# Renesas_Raspi1_Add_On_V2.net
KiCad netlist of a schematic drawn in EAGLE
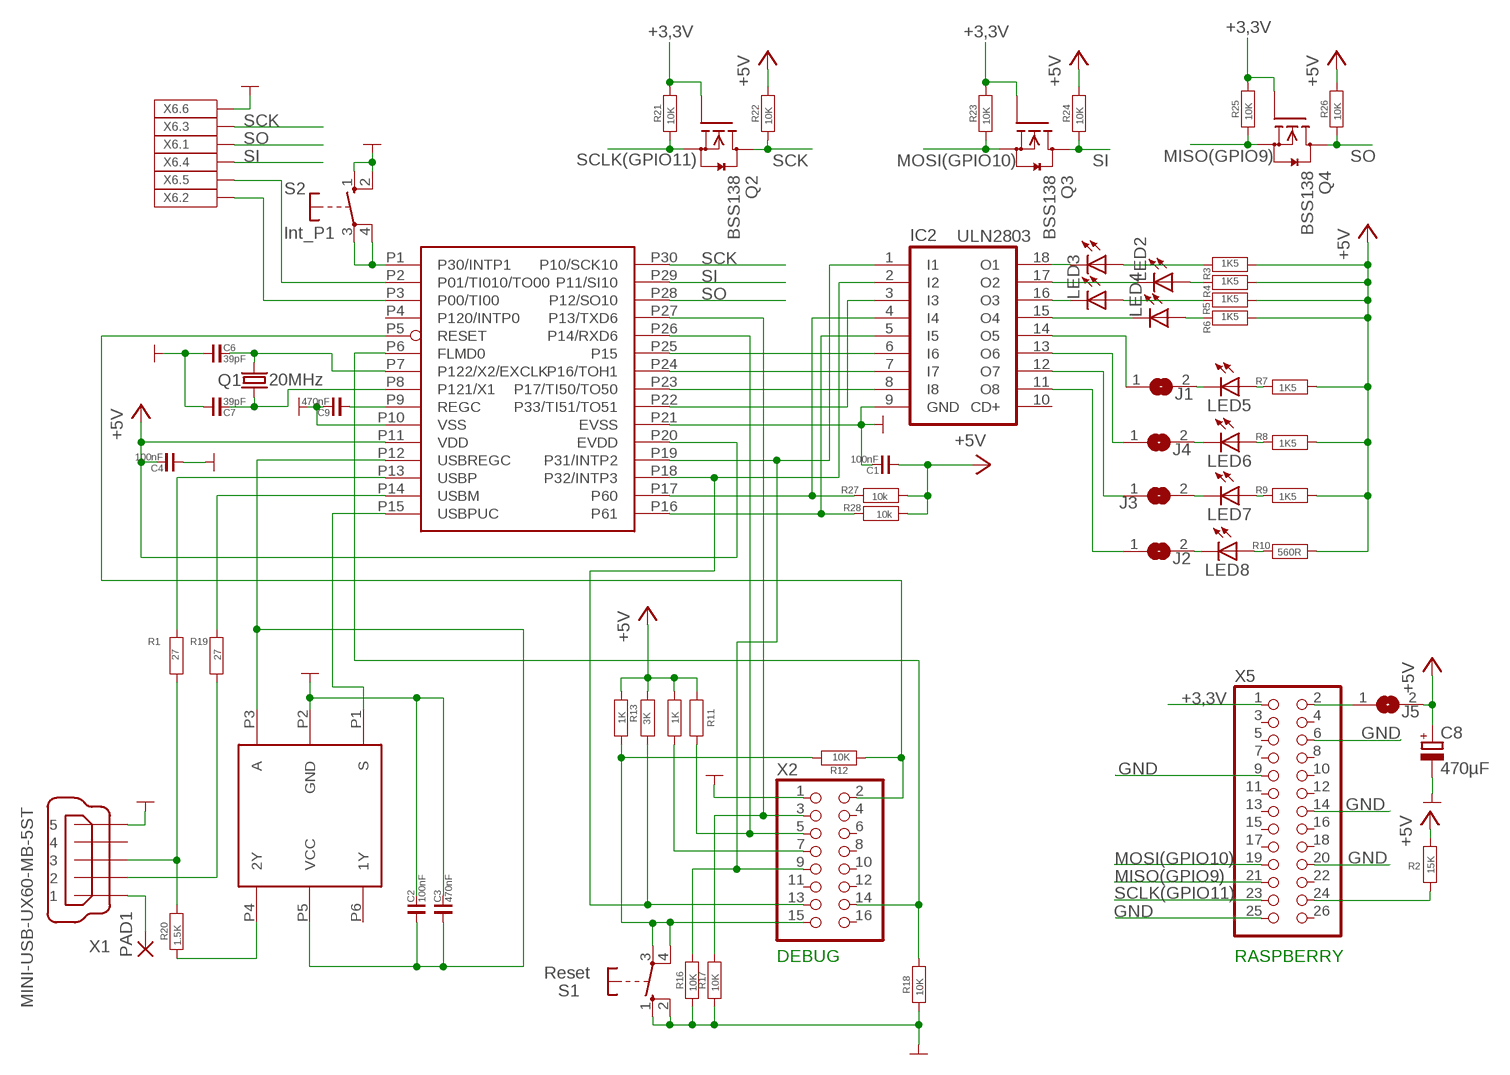
[diagram p0: schematic, sheet 1]

(export (version "E")
  (design (tool "Eeschema 10.0.6"))
  (components
    (comp (ref "C1")
      (value "100nF")
      (footprint "eagle-import:0603")
      (libsource (lib "eagle-import") (part "C-0603"))
    )
    (comp (ref "C2")
      (value "100nF")
      (footprint "eagle-import:0603")
      (libsource (lib "eagle-import") (part "C-0603"))
    )
    (comp (ref "C3")
      (value "470nF")
      (footprint "eagle-import:0603")
      (libsource (lib "eagle-import") (part "C-0603"))
    )
    (comp (ref "C4")
      (value "100nF")
      (footprint "eagle-import:0603")
      (libsource (lib "eagle-import") (part "C-0603"))
    )
    (comp (ref "C6")
      (value "39pF")
      (footprint "eagle-import:0603")
      (libsource (lib "eagle-import") (part "C-0603"))
    )
    (comp (ref "C7")
      (value "39pF")
      (footprint "eagle-import:0603")
      (libsource (lib "eagle-import") (part "C-0603"))
    )
    (comp (ref "C8")
      (value "470µF")
      (footprint "eagle-import:SANYO-OSCON_SMD_F8")
      (libsource (lib "eagle-import") (part "CPOL-EUSANYO_SMD_F8"))
    )
    (comp (ref "C9")
      (value "470nF")
      (footprint "eagle-import:0603")
      (libsource (lib "eagle-import") (part "C-0603"))
    )
    (comp (ref "IC1")
      (value "78F0730_CAB_AX")
      (footprint "eagle-import:SSOP30")
      (libsource (lib "eagle-import") (part "78F0730_CAB_AX"))
    )
    (comp (ref "IC2")
      (value "ULN2803")
      (footprint "eagle-import:SOJ18-4")
      (libsource (lib "eagle-import") (part "ULN2803"))
    )
    (comp (ref "IC3")
      (value "74LVC1G18")
      (footprint "eagle-import:74LVC1G18")
      (libsource (lib "eagle-import") (part "74LVC1G18"))
    )
    (comp (ref "J1") (value "SJ") (footprint "eagle-import:SJ") (libsource (lib "eagle-import") (part "SJ")))
    (comp (ref "J2") (value "SJ") (footprint "eagle-import:SJ") (libsource (lib "eagle-import") (part "SJ")))
    (comp (ref "J3") (value "SJ") (footprint "eagle-import:SJ") (libsource (lib "eagle-import") (part "SJ")))
    (comp (ref "J4") (value "SJ") (footprint "eagle-import:SJ") (libsource (lib "eagle-import") (part "SJ")))
    (comp (ref "J5") (value "SJ") (footprint "eagle-import:SJ") (libsource (lib "eagle-import") (part "SJ")))
    (comp (ref "LED1")
      (value "LEDCHIP-LED0603")
      (footprint "eagle-import:CHIP-LED0603")
      (libsource (lib "eagle-import") (part "LEDCHIP-LED0603"))
    )
    (comp (ref "LED2")
      (value "LEDCHIP-LED0603")
      (footprint "eagle-import:CHIP-LED0603")
      (libsource (lib "eagle-import") (part "LEDCHIP-LED0603"))
    )
    (comp (ref "LED3")
      (value "LEDCHIP-LED0603")
      (footprint "eagle-import:CHIP-LED0603")
      (libsource (lib "eagle-import") (part "LEDCHIP-LED0603"))
    )
    (comp (ref "LED4")
      (value "LEDCHIP-LED0603")
      (footprint "eagle-import:CHIP-LED0603")
      (libsource (lib "eagle-import") (part "LEDCHIP-LED0603"))
    )
    (comp (ref "LED5")
      (value "LEDCHIP-LED0603")
      (footprint "eagle-import:CHIP-LED0603")
      (libsource (lib "eagle-import") (part "LEDCHIP-LED0603"))
    )
    (comp (ref "LED6")
      (value "LEDCHIP-LED0603")
      (footprint "eagle-import:CHIP-LED0603")
      (libsource (lib "eagle-import") (part "LEDCHIP-LED0603"))
    )
    (comp (ref "LED7")
      (value "LEDCHIP-LED0603")
      (footprint "eagle-import:CHIP-LED0603")
      (libsource (lib "eagle-import") (part "LEDCHIP-LED0603"))
    )
    (comp (ref "LED8")
      (value "LEDCHIP-LED0603")
      (footprint "eagle-import:CHIP-LED0603")
      (libsource (lib "eagle-import") (part "LEDCHIP-LED0603"))
    )
    (comp (ref "PAD1")
      (value "1,6/0,8")
      (footprint "eagle-import:1,6_0,8")
      (libsource (lib "eagle-import") (part "1,6/0,8"))
    )
    (comp (ref "Q1")
      (value "20MHz")
      (footprint "eagle-import:HC49UP")
      (libsource (lib "eagle-import") (part "CRYSTALHC49UP"))
    )
    (comp (ref "Q2")
      (value "BSS138")
      (footprint "eagle-import:SOT23")
      (libsource (lib "eagle-import") (part "BSS138"))
    )
    (comp (ref "Q3")
      (value "BSS138")
      (footprint "eagle-import:SOT23")
      (libsource (lib "eagle-import") (part "BSS138"))
    )
    (comp (ref "Q4")
      (value "BSS138")
      (footprint "eagle-import:SOT23")
      (libsource (lib "eagle-import") (part "BSS138"))
    )
    (comp (ref "R1")
      (value "27")
      (footprint "eagle-import:0603")
      (libsource (lib "eagle-import") (part "R-0603"))
    )
    (comp (ref "R2")
      (value "15K")
      (footprint "eagle-import:0603")
      (libsource (lib "eagle-import") (part "R-0603"))
    )
    (comp (ref "R3")
      (value "1K5")
      (footprint "eagle-import:0603")
      (libsource (lib "eagle-import") (part "R-0603"))
    )
    (comp (ref "R4")
      (value "1K5")
      (footprint "eagle-import:0603")
      (libsource (lib "eagle-import") (part "R-0603"))
    )
    (comp (ref "R5")
      (value "1K5")
      (footprint "eagle-import:0603")
      (libsource (lib "eagle-import") (part "R-0603"))
    )
    (comp (ref "R6")
      (value "1K5")
      (footprint "eagle-import:0603")
      (libsource (lib "eagle-import") (part "R-0603"))
    )
    (comp (ref "R7")
      (value "1K5")
      (footprint "eagle-import:0603")
      (libsource (lib "eagle-import") (part "R-0603"))
    )
    (comp (ref "R8")
      (value "1K5")
      (footprint "eagle-import:0603")
      (libsource (lib "eagle-import") (part "R-0603"))
    )
    (comp (ref "R9")
      (value "1K5")
      (footprint "eagle-import:0603")
      (libsource (lib "eagle-import") (part "R-0603"))
    )
    (comp (ref "R10")
      (value "560R")
      (footprint "eagle-import:0603")
      (libsource (lib "eagle-import") (part "R-0603"))
    )
    (comp (ref "R11")
      (value "3K")
      (footprint "eagle-import:0603")
      (libsource (lib "eagle-import") (part "R-0603"))
    )
    (comp (ref "R12")
      (value "10K")
      (footprint "eagle-import:0603")
      (libsource (lib "eagle-import") (part "R-0603"))
    )
    (comp (ref "R13")
      (value "3K")
      (footprint "eagle-import:0603")
      (libsource (lib "eagle-import") (part "R-0603"))
    )
    (comp (ref "R14")
      (value "1K")
      (footprint "eagle-import:0603")
      (libsource (lib "eagle-import") (part "R-0603"))
    )
    (comp (ref "R15")
      (value "1K")
      (footprint "eagle-import:0603")
      (libsource (lib "eagle-import") (part "R-0603"))
    )
    (comp (ref "R16")
      (value "10K")
      (footprint "eagle-import:0603")
      (libsource (lib "eagle-import") (part "R-0603"))
    )
    (comp (ref "R17")
      (value "10K")
      (footprint "eagle-import:0603")
      (libsource (lib "eagle-import") (part "R-0603"))
    )
    (comp (ref "R18")
      (value "10K")
      (footprint "eagle-import:0603")
      (libsource (lib "eagle-import") (part "R-0603"))
    )
    (comp (ref "R19")
      (value "27")
      (footprint "eagle-import:0603")
      (libsource (lib "eagle-import") (part "R-0603"))
    )
    (comp (ref "R20")
      (value "1.5K")
      (footprint "eagle-import:0603")
      (libsource (lib "eagle-import") (part "R-0603"))
    )
    (comp (ref "R21")
      (value "10K")
      (footprint "eagle-import:0603")
      (libsource (lib "eagle-import") (part "R-0603"))
    )
    (comp (ref "R22")
      (value "10K")
      (footprint "eagle-import:0603")
      (libsource (lib "eagle-import") (part "R-0603"))
    )
    (comp (ref "R23")
      (value "10K")
      (footprint "eagle-import:0603")
      (libsource (lib "eagle-import") (part "R-0603"))
    )
    (comp (ref "R24")
      (value "10K")
      (footprint "eagle-import:0603")
      (libsource (lib "eagle-import") (part "R-0603"))
    )
    (comp (ref "R25")
      (value "10K")
      (footprint "eagle-import:0603")
      (libsource (lib "eagle-import") (part "R-0603"))
    )
    (comp (ref "R26")
      (value "10K")
      (footprint "eagle-import:0603")
      (libsource (lib "eagle-import") (part "R-0603"))
    )
    (comp (ref "R27")
      (value "10k")
      (footprint "eagle-import:0603")
      (libsource (lib "eagle-import") (part "R-0603"))
    )
    (comp (ref "R28")
      (value "10k")
      (footprint "eagle-import:0603")
      (libsource (lib "eagle-import") (part "R-0603"))
    )
    (comp (ref "S1")
      (value "Reset")
      (footprint "eagle-import:DT6")
      (libsource (lib "eagle-import") (part "DT6"))
    )
    (comp (ref "S2")
      (value "Int_P1")
      (footprint "eagle-import:DT6")
      (libsource (lib "eagle-import") (part "DT6"))
    )
    (comp (ref "X1")
      (value "MINI-USB-UX60-MB-5ST")
      (footprint "eagle-import:UX60-MB-5ST")
      (libsource (lib "eagle-import") (part "MINI-USB-UX60-MB-5ST"))
    )
    (comp (ref "X2")
      (value "PINHD-2X8")
      (footprint "eagle-import:2X08")
      (libsource (lib "eagle-import") (part "PINHD-2X8"))
    )
    (comp (ref "X5")
      (value "PINHD-2X13")
      (footprint "eagle-import:2X13")
      (libsource (lib "eagle-import") (part "PINHD-2X13"))
    )
    (comp (ref "X6")
      (value "2X3")
      (footprint "eagle-import:2X3")
      (libsource (lib "eagle-import") (part "2X3"))
    )
  )
  (nets
    (net (code "1") (name "+5V") (class "Default")
      (node (ref "C1") (pin "1") (pinfunction "1_1") (pintype "passive"))
      (node (ref "C4") (pin "2") (pinfunction "2_2") (pintype "passive"))
      (node (ref "C8") (pin "+") (pinfunction "+_+") (pintype "passive"))
      (node (ref "IC1") (pin "P11") (pinfunction "VDD_P11") (pintype "bidirectional"))
      (node (ref "IC1") (pin "P20") (pinfunction "EVDD_P20") (pintype "bidirectional"))
      (node (ref "J5") (pin "2") (pinfunction "2_2") (pintype "passive"))
      (node (ref "R10") (pin "1") (pinfunction "1_1") (pintype "passive"))
      (node (ref "R11") (pin "1") (pinfunction "1_1") (pintype "passive"))
      (node (ref "R13") (pin "2") (pinfunction "2_2") (pintype "passive"))
      (node (ref "R14") (pin "1") (pinfunction "1_1") (pintype "passive"))
      (node (ref "R15") (pin "1") (pinfunction "1_1") (pintype "passive"))
      (node (ref "R2") (pin "1") (pinfunction "1_1") (pintype "passive"))
      (node (ref "R22") (pin "1") (pinfunction "1_1") (pintype "passive"))
      (node (ref "R24") (pin "1") (pinfunction "1_1") (pintype "passive"))
      (node (ref "R26") (pin "1") (pinfunction "1_1") (pintype "passive"))
      (node (ref "R27") (pin "1") (pinfunction "1_1") (pintype "passive"))
      (node (ref "R28") (pin "1") (pinfunction "1_1") (pintype "passive"))
      (node (ref "R3") (pin "2") (pinfunction "2_2") (pintype "passive"))
      (node (ref "R4") (pin "2") (pinfunction "2_2") (pintype "passive"))
      (node (ref "R5") (pin "2") (pinfunction "2_2") (pintype "passive"))
      (node (ref "R6") (pin "2") (pinfunction "2_2") (pintype "passive"))
      (node (ref "R7") (pin "1") (pinfunction "1_1") (pintype "passive"))
      (node (ref "R8") (pin "1") (pinfunction "1_1") (pintype "passive"))
      (node (ref "R9") (pin "1") (pinfunction "1_1") (pintype "passive"))
    )
    (net (code "2") (name "/+3,3V") (class "Default")
      (node (ref "Q2") (pin "1") (pinfunction "G_1") (pintype "passive"))
      (node (ref "Q3") (pin "1") (pinfunction "G_1") (pintype "passive"))
      (node (ref "Q4") (pin "1") (pinfunction "G_1") (pintype "passive"))
      (node (ref "R21") (pin "1") (pinfunction "1_1") (pintype "passive"))
      (node (ref "R23") (pin "1") (pinfunction "1_1") (pintype "passive"))
      (node (ref "R25") (pin "1") (pinfunction "1_1") (pintype "passive"))
      (node (ref "X5") (pin "1") (pinfunction "1_1") (pintype "passive"))
    )
    (net (code "3") (name "/MISO(GPIO9)") (class "Default")
      (node (ref "Q4") (pin "2") (pinfunction "S_2") (pintype "passive"))
      (node (ref "R25") (pin "2") (pinfunction "2_2") (pintype "passive"))
      (node (ref "X5") (pin "21") (pinfunction "21_21") (pintype "passive"))
    )
    (net (code "4") (name "/MOSI(GPIO10)") (class "Default")
      (node (ref "Q3") (pin "2") (pinfunction "S_2") (pintype "passive"))
      (node (ref "R23") (pin "2") (pinfunction "2_2") (pintype "passive"))
      (node (ref "X5") (pin "19") (pinfunction "19_19") (pintype "passive"))
    )
    (net (code "5") (name "/N$14") (class "Default")
      (node (ref "R12") (pin "1") (pinfunction "1_1") (pintype "passive"))
      (node (ref "R15") (pin "2") (pinfunction "2_2") (pintype "passive"))
      (node (ref "S1") (pin "3") (pinfunction "P_3") (pintype "passive"))
      (node (ref "S1") (pin "4") (pinfunction "P_4") (pintype "passive"))
      (node (ref "X2") (pin "15") (pinfunction "15_15") (pintype "passive"))
    )
    (net (code "6") (name "/SCK") (class "Default")
      (node (ref "IC1") (pin "P30") (pinfunction "P10/SCK10_P30") (pintype "bidirectional"))
      (node (ref "Q2") (pin "3") (pinfunction "D_3") (pintype "passive"))
      (node (ref "R22") (pin "2") (pinfunction "2_2") (pintype "passive"))
      (node (ref "X6") (pin "3") (pinfunction "I_3") (pintype "passive"))
    )
    (net (code "7") (name "/SCLK(GPIO11)") (class "Default")
      (node (ref "Q2") (pin "2") (pinfunction "S_2") (pintype "passive"))
      (node (ref "R21") (pin "2") (pinfunction "2_2") (pintype "passive"))
      (node (ref "X5") (pin "23") (pinfunction "23_23") (pintype "passive"))
    )
    (net (code "8") (name "/SI") (class "Default")
      (node (ref "IC1") (pin "P29") (pinfunction "P11/SI10_P29") (pintype "bidirectional"))
      (node (ref "Q3") (pin "3") (pinfunction "D_3") (pintype "passive"))
      (node (ref "R24") (pin "2") (pinfunction "2_2") (pintype "passive"))
      (node (ref "X6") (pin "4") (pinfunction "I_4") (pintype "passive"))
    )
    (net (code "9") (name "/SO") (class "Default")
      (node (ref "IC1") (pin "P28") (pinfunction "P12/SO10_P28") (pintype "bidirectional"))
      (node (ref "Q4") (pin "3") (pinfunction "D_3") (pintype "passive"))
      (node (ref "R26") (pin "2") (pinfunction "2_2") (pintype "passive"))
      (node (ref "X6") (pin "1") (pinfunction "I_1") (pintype "passive"))
    )
    (net (code "10") (name "GND") (class "Default")
      (node (ref "C1") (pin "2") (pinfunction "2_2") (pintype "passive"))
      (node (ref "C2") (pin "2") (pinfunction "2_2") (pintype "passive"))
      (node (ref "C3") (pin "2") (pinfunction "2_2") (pintype "passive"))
      (node (ref "C4") (pin "1") (pinfunction "1_1") (pintype "passive"))
      (node (ref "C6") (pin "1") (pinfunction "1_1") (pintype "passive"))
      (node (ref "C7") (pin "1") (pinfunction "1_1") (pintype "passive"))
      (node (ref "C8") (pin "-") (pinfunction "-_-") (pintype "passive"))
      (node (ref "C9") (pin "2") (pinfunction "2_2") (pintype "passive"))
      (node (ref "IC1") (pin "P10") (pinfunction "VSS_P10") (pintype "bidirectional"))
      (node (ref "IC1") (pin "P21") (pinfunction "EVSS_P21") (pintype "bidirectional"))
      (node (ref "IC2") (pin "9") (pinfunction "GND_9") (pintype "power_in"))
      (node (ref "IC3") (pin "P2") (pinfunction "GND_P2") (pintype "bidirectional"))
      (node (ref "R16") (pin "2") (pinfunction "2_2") (pintype "passive"))
      (node (ref "R17") (pin "2") (pinfunction "2_2") (pintype "passive"))
      (node (ref "R18") (pin "2") (pinfunction "2_2") (pintype "passive"))
      (node (ref "S1") (pin "1") (pinfunction "S_1") (pintype "passive"))
      (node (ref "S1") (pin "2") (pinfunction "S_2") (pintype "passive"))
      (node (ref "S2") (pin "1") (pinfunction "S_1") (pintype "passive"))
      (node (ref "S2") (pin "2") (pinfunction "S_2") (pintype "passive"))
      (node (ref "X1") (pin "5") (pinfunction "5_5") (pintype "input"))
      (node (ref "X2") (pin "1") (pinfunction "1_1") (pintype "passive"))
      (node (ref "X5") (pin "14") (pinfunction "14_14") (pintype "passive"))
      (node (ref "X5") (pin "20") (pinfunction "20_20") (pintype "passive"))
      (node (ref "X5") (pin "25") (pinfunction "25_25") (pintype "passive"))
      (node (ref "X5") (pin "6") (pinfunction "6_6") (pintype "passive"))
      (node (ref "X5") (pin "9") (pinfunction "9_9") (pintype "passive"))
      (node (ref "X6") (pin "6") (pinfunction "I_6") (pintype "passive"))
    )
    (net (code "11") (name "Net-(IC1-FLMD0)") (class "Default")
      (node (ref "IC1") (pin "P6") (pinfunction "FLMD0_P6") (pintype "bidirectional"))
      (node (ref "R18") (pin "1") (pinfunction "1_1") (pintype "passive"))
      (node (ref "X2") (pin "14") (pinfunction "14_14") (pintype "passive"))
    )
    (net (code "12") (name "Net-(IC1-P00{slash}TI00)") (class "Default")
      (node (ref "IC1") (pin "P3") (pinfunction "P00/TI00_P3") (pintype "bidirectional"))
      (node (ref "X6") (pin "2") (pinfunction "I_2") (pintype "passive"))
    )
    (net (code "13") (name "Net-(IC1-P01{slash}TI010{slash}TO00)") (class "Default")
      (node (ref "IC1") (pin "P2") (pinfunction "P01/TI010/TO00_P2") (pintype "bidirectional"))
      (node (ref "X6") (pin "5") (pinfunction "I_5") (pintype "passive"))
    )
    (net (code "14") (name "Net-(IC1-P13{slash}TXD6)") (class "Default")
      (node (ref "IC1") (pin "P27") (pinfunction "P13/TXD6_P27") (pintype "bidirectional"))
      (node (ref "R17") (pin "1") (pinfunction "1_1") (pintype "passive"))
      (node (ref "X2") (pin "3") (pinfunction "3_3") (pintype "passive"))
    )
    (net (code "15") (name "Net-(IC1-P14{slash}RXD6)") (class "Default")
      (node (ref "IC1") (pin "P26") (pinfunction "P14/RXD6_P26") (pintype "bidirectional"))
      (node (ref "R11") (pin "2") (pinfunction "2_2") (pintype "passive"))
      (node (ref "X2") (pin "5") (pinfunction "5_5") (pintype "passive"))
    )
    (net (code "16") (name "Net-(IC1-P15)") (class "Default")
      (node (ref "IC1") (pin "P25") (pinfunction "P15_P25") (pintype "bidirectional"))
      (node (ref "IC2") (pin "6") (pinfunction "I6_6") (pintype "input"))
    )
    (net (code "17") (name "Net-(IC1-P16{slash}TOH1)") (class "Default")
      (node (ref "IC1") (pin "P24") (pinfunction "P16/TOH1_P24") (pintype "bidirectional"))
      (node (ref "IC2") (pin "7") (pinfunction "I7_7") (pintype "input"))
    )
    (net (code "18") (name "Net-(IC1-P17{slash}TI50{slash}TO50)") (class "Default")
      (node (ref "IC1") (pin "P23") (pinfunction "P17/TI50/TO50_P23") (pintype "bidirectional"))
      (node (ref "IC2") (pin "8") (pinfunction "I8_8") (pintype "input"))
    )
    (net (code "19") (name "Net-(IC1-P30{slash}INTP1)") (class "Default")
      (node (ref "IC1") (pin "P1") (pinfunction "P30/INTP1_P1") (pintype "bidirectional"))
      (node (ref "S2") (pin "3") (pinfunction "P_3") (pintype "passive"))
      (node (ref "S2") (pin "4") (pinfunction "P_4") (pintype "passive"))
    )
    (net (code "20") (name "Net-(IC1-P31{slash}INTP2)") (class "Default")
      (node (ref "IC1") (pin "P19") (pinfunction "P31/INTP2_P19") (pintype "bidirectional"))
      (node (ref "IC2") (pin "1") (pinfunction "I1_1") (pintype "input"))
      (node (ref "R16") (pin "1") (pinfunction "1_1") (pintype "passive"))
      (node (ref "X2") (pin "9") (pinfunction "9_9") (pintype "passive"))
    )
    (net (code "21") (name "Net-(IC1-P32{slash}INTP3)") (class "Default")
      (node (ref "IC1") (pin "P18") (pinfunction "P32/INTP3_P18") (pintype "bidirectional"))
      (node (ref "IC2") (pin "2") (pinfunction "I2_2") (pintype "input"))
      (node (ref "R13") (pin "1") (pinfunction "1_1") (pintype "passive"))
      (node (ref "X2") (pin "13") (pinfunction "13_13") (pintype "passive"))
    )
    (net (code "22") (name "Net-(IC1-P33{slash}TI51{slash}TO51)") (class "Default")
      (node (ref "IC1") (pin "P22") (pinfunction "P33/TI51/TO51_P22") (pintype "bidirectional"))
      (node (ref "IC2") (pin "3") (pinfunction "I3_3") (pintype "input"))
    )
    (net (code "23") (name "Net-(IC1-P60)") (class "Default")
      (node (ref "IC1") (pin "P17") (pinfunction "P60_P17") (pintype "bidirectional"))
      (node (ref "IC2") (pin "4") (pinfunction "I4_4") (pintype "input"))
      (node (ref "R27") (pin "2") (pinfunction "2_2") (pintype "passive"))
    )
    (net (code "24") (name "Net-(IC1-P61)") (class "Default")
      (node (ref "IC1") (pin "P16") (pinfunction "P61_P16") (pintype "bidirectional"))
      (node (ref "IC2") (pin "5") (pinfunction "I5_5") (pintype "input"))
      (node (ref "R28") (pin "2") (pinfunction "2_2") (pintype "passive"))
    )
    (net (code "25") (name "Net-(IC1-P121{slash}X1)") (class "Default")
      (node (ref "C7") (pin "2") (pinfunction "2_2") (pintype "passive"))
      (node (ref "IC1") (pin "P8") (pinfunction "P121/X1_P8") (pintype "bidirectional"))
      (node (ref "Q1") (pin "1") (pinfunction "1_1") (pintype "passive"))
    )
    (net (code "26") (name "Net-(IC1-P122{slash}X2{slash}EXCLK)") (class "Default")
      (node (ref "C6") (pin "2") (pinfunction "2_2") (pintype "passive"))
      (node (ref "IC1") (pin "P7") (pinfunction "P122/X2/EXCLK_P7") (pintype "bidirectional"))
      (node (ref "Q1") (pin "2") (pinfunction "2_2") (pintype "passive"))
    )
    (net (code "27") (name "Net-(IC1-REGC)") (class "Default")
      (node (ref "C9") (pin "1") (pinfunction "1_1") (pintype "passive"))
      (node (ref "IC1") (pin "P9") (pinfunction "REGC_P9") (pintype "bidirectional"))
    )
    (net (code "28") (name "Net-(IC1-RESET)") (class "Default")
      (node (ref "IC1") (pin "P5") (pinfunction "RESET_P5") (pintype "bidirectional"))
      (node (ref "R12") (pin "2") (pinfunction "2_2") (pintype "passive"))
      (node (ref "X2") (pin "2") (pinfunction "2_2") (pintype "passive"))
    )
    (net (code "29") (name "Net-(IC1-USBM)") (class "Default")
      (node (ref "IC1") (pin "P14") (pinfunction "USBM_P14") (pintype "bidirectional"))
      (node (ref "R19") (pin "1") (pinfunction "1_1") (pintype "passive"))
    )
    (net (code "30") (name "Net-(IC1-USBP)") (class "Default")
      (node (ref "IC1") (pin "P13") (pinfunction "USBP_P13") (pintype "bidirectional"))
      (node (ref "R1") (pin "1") (pinfunction "1_1") (pintype "passive"))
    )
    (net (code "31") (name "Net-(IC1-USBPUC)") (class "Default")
      (node (ref "IC1") (pin "P15") (pinfunction "USBPUC_P15") (pintype "bidirectional"))
      (node (ref "IC3") (pin "P1") (pinfunction "S_P1") (pintype "bidirectional"))
    )
    (net (code "32") (name "Net-(IC1-USBREGC)") (class "Default")
      (node (ref "C2") (pin "1") (pinfunction "1_1") (pintype "passive"))
      (node (ref "C3") (pin "1") (pinfunction "1_1") (pintype "passive"))
      (node (ref "IC1") (pin "P12") (pinfunction "USBREGC_P12") (pintype "bidirectional"))
      (node (ref "IC3") (pin "P3") (pinfunction "A_P3") (pintype "bidirectional"))
      (node (ref "IC3") (pin "P5") (pinfunction "VCC_P5") (pintype "bidirectional"))
    )
    (net (code "33") (name "Net-(IC2-O1)") (class "Default")
      (node (ref "IC2") (pin "18") (pinfunction "O1_18") (pintype "open_collector"))
      (node (ref "LED1") (pin "C") (pinfunction "C_C") (pintype "passive"))
    )
    (net (code "34") (name "Net-(IC2-O2)") (class "Default")
      (node (ref "IC2") (pin "17") (pinfunction "O2_17") (pintype "open_collector"))
      (node (ref "LED2") (pin "C") (pinfunction "C_C") (pintype "passive"))
    )
    (net (code "35") (name "Net-(IC2-O3)") (class "Default")
      (node (ref "IC2") (pin "16") (pinfunction "O3_16") (pintype "open_collector"))
      (node (ref "LED3") (pin "C") (pinfunction "C_C") (pintype "passive"))
    )
    (net (code "36") (name "Net-(IC2-O4)") (class "Default")
      (node (ref "IC2") (pin "15") (pinfunction "O4_15") (pintype "open_collector"))
      (node (ref "LED4") (pin "C") (pinfunction "C_C") (pintype "passive"))
    )
    (net (code "37") (name "Net-(IC2-O5)") (class "Default")
      (node (ref "IC2") (pin "14") (pinfunction "O5_14") (pintype "open_collector"))
      (node (ref "J1") (pin "1") (pinfunction "1_1") (pintype "passive"))
    )
    (net (code "38") (name "Net-(IC2-O6)") (class "Default")
      (node (ref "IC2") (pin "13") (pinfunction "O6_13") (pintype "open_collector"))
      (node (ref "J4") (pin "1") (pinfunction "1_1") (pintype "passive"))
    )
    (net (code "39") (name "Net-(IC2-O7)") (class "Default")
      (node (ref "IC2") (pin "12") (pinfunction "O7_12") (pintype "open_collector"))
      (node (ref "J3") (pin "1") (pinfunction "1_1") (pintype "passive"))
    )
    (net (code "40") (name "Net-(IC2-O8)") (class "Default")
      (node (ref "IC2") (pin "11") (pinfunction "O8_11") (pintype "open_collector"))
      (node (ref "J2") (pin "1") (pinfunction "1_1") (pintype "passive"))
    )
    (net (code "41") (name "Net-(IC3-2Y)") (class "Default")
      (node (ref "IC3") (pin "P4") (pinfunction "2Y_P4") (pintype "bidirectional"))
      (node (ref "R20") (pin "2") (pinfunction "2_2") (pintype "passive"))
    )
    (net (code "42") (name "Net-(J1-Pad2)") (class "Default")
      (node (ref "J1") (pin "2") (pinfunction "2_2") (pintype "passive"))
      (node (ref "LED5") (pin "C") (pinfunction "C_C") (pintype "passive"))
    )
    (net (code "43") (name "Net-(J2-Pad2)") (class "Default")
      (node (ref "J2") (pin "2") (pinfunction "2_2") (pintype "passive"))
      (node (ref "LED8") (pin "C") (pinfunction "C_C") (pintype "passive"))
    )
    (net (code "44") (name "Net-(J3-Pad2)") (class "Default")
      (node (ref "J3") (pin "2") (pinfunction "2_2") (pintype "passive"))
      (node (ref "LED7") (pin "C") (pinfunction "C_C") (pintype "passive"))
    )
    (net (code "45") (name "Net-(J4-Pad2)") (class "Default")
      (node (ref "J4") (pin "2") (pinfunction "2_2") (pintype "passive"))
      (node (ref "LED6") (pin "C") (pinfunction "C_C") (pintype "passive"))
    )
    (net (code "46") (name "Net-(J5-Pad1)") (class "Default")
      (node (ref "J5") (pin "1") (pinfunction "1_1") (pintype "passive"))
      (node (ref "X5") (pin "2") (pinfunction "2_2") (pintype "passive"))
    )
    (net (code "47") (name "Net-(LED1-PadA)") (class "Default")
      (node (ref "LED1") (pin "A") (pinfunction "A_A") (pintype "passive"))
      (node (ref "R3") (pin "1") (pinfunction "1_1") (pintype "passive"))
    )
    (net (code "48") (name "Net-(LED2-PadA)") (class "Default")
      (node (ref "LED2") (pin "A") (pinfunction "A_A") (pintype "passive"))
      (node (ref "R4") (pin "1") (pinfunction "1_1") (pintype "passive"))
    )
    (net (code "49") (name "Net-(LED3-PadA)") (class "Default")
      (node (ref "LED3") (pin "A") (pinfunction "A_A") (pintype "passive"))
      (node (ref "R5") (pin "1") (pinfunction "1_1") (pintype "passive"))
    )
    (net (code "50") (name "Net-(LED4-PadA)") (class "Default")
      (node (ref "LED4") (pin "A") (pinfunction "A_A") (pintype "passive"))
      (node (ref "R6") (pin "1") (pinfunction "1_1") (pintype "passive"))
    )
    (net (code "51") (name "Net-(LED5-PadA)") (class "Default")
      (node (ref "LED5") (pin "A") (pinfunction "A_A") (pintype "passive"))
      (node (ref "R7") (pin "2") (pinfunction "2_2") (pintype "passive"))
    )
    (net (code "52") (name "Net-(LED6-PadA)") (class "Default")
      (node (ref "LED6") (pin "A") (pinfunction "A_A") (pintype "passive"))
      (node (ref "R8") (pin "2") (pinfunction "2_2") (pintype "passive"))
    )
    (net (code "53") (name "Net-(LED7-PadA)") (class "Default")
      (node (ref "LED7") (pin "A") (pinfunction "A_A") (pintype "passive"))
      (node (ref "R9") (pin "2") (pinfunction "2_2") (pintype "passive"))
    )
    (net (code "54") (name "Net-(LED8-PadA)") (class "Default")
      (node (ref "LED8") (pin "A") (pinfunction "A_A") (pintype "passive"))
      (node (ref "R10") (pin "2") (pinfunction "2_2") (pintype "passive"))
    )
    (net (code "55") (name "Net-(PAD1-P)") (class "Default")
      (node (ref "PAD1") (pin "1") (pinfunction "P_1") (pintype "passive"))
      (node (ref "X1") (pin "1") (pinfunction "1_1") (pintype "input"))
    )
    (net (code "56") (name "Net-(R1-Pad2)") (class "Default")
      (node (ref "R1") (pin "2") (pinfunction "2_2") (pintype "passive"))
      (node (ref "R20") (pin "1") (pinfunction "1_1") (pintype "passive"))
      (node (ref "X1") (pin "3") (pinfunction "3_3") (pintype "input"))
    )
    (net (code "57") (name "Net-(R2-Pad2)") (class "Default")
      (node (ref "R2") (pin "2") (pinfunction "2_2") (pintype "passive"))
      (node (ref "X5") (pin "24") (pinfunction "24_24") (pintype "passive"))
    )
    (net (code "58") (name "Net-(R14-Pad2)") (class "Default")
      (node (ref "R14") (pin "2") (pinfunction "2_2") (pintype "passive"))
      (node (ref "X2") (pin "7") (pinfunction "7_7") (pintype "passive"))
    )
    (net (code "59") (name "Net-(R19-Pad2)") (class "Default")
      (node (ref "R19") (pin "2") (pinfunction "2_2") (pintype "passive"))
      (node (ref "X1") (pin "2") (pinfunction "2_2") (pintype "input"))
    )
    (net (code "60") (name "unconnected-(IC1-P120{slash}INTP0-PadP4)") (class "Default")
      (node (ref "IC1") (pin "P4") (pinfunction "P120/INTP0_P4") (pintype "bidirectional"))
    )
    (net (code "61") (name "unconnected-(IC2-CD+-Pad10)") (class "Default")
      (node (ref "IC2") (pin "10") (pinfunction "CD+_10") (pintype "passive"))
    )
    (net (code "62") (name "unconnected-(IC3-1Y-PadP6)") (class "Default")
      (node (ref "IC3") (pin "P6") (pinfunction "1Y_P6") (pintype "bidirectional"))
    )
    (net (code "63") (name "unconnected-(X1-Pad4)") (class "Default")
      (node (ref "X1") (pin "4") (pinfunction "4_4") (pintype "input"))
    )
    (net (code "64") (name "unconnected-(X2-Pad4)") (class "Default")
      (node (ref "X2") (pin "4") (pinfunction "4_4") (pintype "passive"))
    )
    (net (code "65") (name "unconnected-(X2-Pad6)") (class "Default")
      (node (ref "X2") (pin "6") (pinfunction "6_6") (pintype "passive"))
    )
    (net (code "66") (name "unconnected-(X2-Pad8)") (class "Default")
      (node (ref "X2") (pin "8") (pinfunction "8_8") (pintype "passive"))
    )
    (net (code "67") (name "unconnected-(X2-Pad10)") (class "Default")
      (node (ref "X2") (pin "10") (pinfunction "10_10") (pintype "passive"))
    )
    (net (code "68") (name "unconnected-(X2-Pad11)") (class "Default")
      (node (ref "X2") (pin "11") (pinfunction "11_11") (pintype "passive"))
    )
    (net (code "69") (name "unconnected-(X2-Pad12)") (class "Default")
      (node (ref "X2") (pin "12") (pinfunction "12_12") (pintype "passive"))
    )
    (net (code "70") (name "unconnected-(X2-Pad16)") (class "Default")
      (node (ref "X2") (pin "16") (pinfunction "16_16") (pintype "passive"))
    )
    (net (code "71") (name "unconnected-(X5-Pad3)") (class "Default")
      (node (ref "X5") (pin "3") (pinfunction "3_3") (pintype "passive"))
    )
    (net (code "72") (name "unconnected-(X5-Pad4)") (class "Default")
      (node (ref "X5") (pin "4") (pinfunction "4_4") (pintype "passive"))
    )
    (net (code "73") (name "unconnected-(X5-Pad5)") (class "Default")
      (node (ref "X5") (pin "5") (pinfunction "5_5") (pintype "passive"))
    )
    (net (code "74") (name "unconnected-(X5-Pad7)") (class "Default")
      (node (ref "X5") (pin "7") (pinfunction "7_7") (pintype "passive"))
    )
    (net (code "75") (name "unconnected-(X5-Pad8)") (class "Default")
      (node (ref "X5") (pin "8") (pinfunction "8_8") (pintype "passive"))
    )
    (net (code "76") (name "unconnected-(X5-Pad10)") (class "Default")
      (node (ref "X5") (pin "10") (pinfunction "10_10") (pintype "passive"))
    )
    (net (code "77") (name "unconnected-(X5-Pad11)") (class "Default")
      (node (ref "X5") (pin "11") (pinfunction "11_11") (pintype "passive"))
    )
    (net (code "78") (name "unconnected-(X5-Pad12)") (class "Default")
      (node (ref "X5") (pin "12") (pinfunction "12_12") (pintype "passive"))
    )
    (net (code "79") (name "unconnected-(X5-Pad13)") (class "Default")
      (node (ref "X5") (pin "13") (pinfunction "13_13") (pintype "passive"))
    )
    (net (code "80") (name "unconnected-(X5-Pad15)") (class "Default")
      (node (ref "X5") (pin "15") (pinfunction "15_15") (pintype "passive"))
    )
    (net (code "81") (name "unconnected-(X5-Pad16)") (class "Default")
      (node (ref "X5") (pin "16") (pinfunction "16_16") (pintype "passive"))
    )
    (net (code "82") (name "unconnected-(X5-Pad17)") (class "Default")
      (node (ref "X5") (pin "17") (pinfunction "17_17") (pintype "passive"))
    )
    (net (code "83") (name "unconnected-(X5-Pad18)") (class "Default")
      (node (ref "X5") (pin "18") (pinfunction "18_18") (pintype "passive"))
    )
    (net (code "84") (name "unconnected-(X5-Pad22)") (class "Default")
      (node (ref "X5") (pin "22") (pinfunction "22_22") (pintype "passive"))
    )
    (net (code "85") (name "unconnected-(X5-Pad26)") (class "Default")
      (node (ref "X5") (pin "26") (pinfunction "26_26") (pintype "passive"))
    )
  )
)
